# untitled.net
KiCad netlist of a schematic drawn in EAGLE
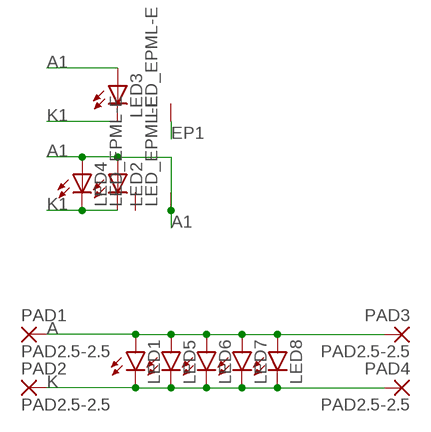
[diagram p0: schematic, sheet 1]

(export (version "E")
  (design (tool "Eeschema 10.0.6"))
  (components
    (comp (ref "LED1")
      (value "LEDSIDELED")
      (footprint "eagle-import:OSRAM-SIDELED")
      (libsource (lib "eagle-import") (part "LEDSIDELED"))
    )
    (comp (ref "LED2")
      (value "LED_EPML-E")
      (footprint "eagle-import:ML-E")
      (libsource (lib "eagle-import") (part "LED_EPML-E"))
    )
    (comp (ref "LED3")
      (value "LED_EPML-E")
      (footprint "eagle-import:ML-E")
      (libsource (lib "eagle-import") (part "LED_EPML-E"))
    )
    (comp (ref "LED4")
      (value "LED_EPML-E")
      (footprint "eagle-import:ML-E")
      (libsource (lib "eagle-import") (part "LED_EPML-E"))
    )
    (comp (ref "LED5")
      (value "LEDSIDELED")
      (footprint "eagle-import:OSRAM-SIDELED")
      (libsource (lib "eagle-import") (part "LEDSIDELED"))
    )
    (comp (ref "LED6")
      (value "LEDSIDELED")
      (footprint "eagle-import:OSRAM-SIDELED")
      (libsource (lib "eagle-import") (part "LEDSIDELED"))
    )
    (comp (ref "LED7")
      (value "LEDSIDELED")
      (footprint "eagle-import:OSRAM-SIDELED")
      (libsource (lib "eagle-import") (part "LEDSIDELED"))
    )
    (comp (ref "LED8")
      (value "LEDSIDELED")
      (footprint "eagle-import:OSRAM-SIDELED")
      (libsource (lib "eagle-import") (part "LEDSIDELED"))
    )
    (comp (ref "PAD1")
      (value "PAD2.5-2.5")
      (footprint "eagle-import:SMD2,5-2,5")
      (libsource (lib "eagle-import") (part "PAD2.5-2.5"))
    )
    (comp (ref "PAD2")
      (value "PAD2.5-2.5")
      (footprint "eagle-import:SMD2,5-2,5")
      (libsource (lib "eagle-import") (part "PAD2.5-2.5"))
    )
    (comp (ref "PAD3")
      (value "PAD2.5-2.5")
      (footprint "eagle-import:SMD2,5-2,5")
      (libsource (lib "eagle-import") (part "PAD2.5-2.5"))
    )
    (comp (ref "PAD4")
      (value "PAD2.5-2.5")
      (footprint "eagle-import:SMD2,5-2,5")
      (libsource (lib "eagle-import") (part "PAD2.5-2.5"))
    )
  )
  (nets
    (net (code "1") (name "/A") (class "Default")
      (node (ref "LED1") (pin "A") (pinfunction "A_A") (pintype "passive"))
      (node (ref "LED5") (pin "A") (pinfunction "A_A") (pintype "passive"))
      (node (ref "LED6") (pin "A") (pinfunction "A_A") (pintype "passive"))
      (node (ref "LED7") (pin "A") (pinfunction "A_A") (pintype "passive"))
      (node (ref "LED8") (pin "A") (pinfunction "A_A") (pintype "passive"))
      (node (ref "PAD1") (pin "1") (pinfunction "P_1") (pintype "passive"))
      (node (ref "PAD3") (pin "1") (pinfunction "P_1") (pintype "passive"))
    )
    (net (code "2") (name "/A1") (class "Default")
      (node (ref "LED2") (pin "A@1") (pinfunction "A_A@1") (pintype "passive"))
      (node (ref "LED2") (pin "A@2") (pinfunction "A_A@2") (pintype "passive"))
      (node (ref "LED2") (pin "TH") (pinfunction "EP_TH") (pintype "passive"))
      (node (ref "LED3") (pin "A@1") (pinfunction "A_A@1") (pintype "passive"))
      (node (ref "LED3") (pin "A@2") (pinfunction "A_A@2") (pintype "passive"))
      (node (ref "LED4") (pin "A@1") (pinfunction "A_A@1") (pintype "passive"))
      (node (ref "LED4") (pin "A@2") (pinfunction "A_A@2") (pintype "passive"))
    )
    (net (code "3") (name "/EP1") (class "Default")
      (node (ref "LED3") (pin "TH") (pinfunction "EP_TH") (pintype "passive"))
    )
    (net (code "4") (name "/K") (class "Default")
      (node (ref "LED1") (pin "C") (pinfunction "C_C") (pintype "passive"))
      (node (ref "LED5") (pin "C") (pinfunction "C_C") (pintype "passive"))
      (node (ref "LED6") (pin "C") (pinfunction "C_C") (pintype "passive"))
      (node (ref "LED7") (pin "C") (pinfunction "C_C") (pintype "passive"))
      (node (ref "LED8") (pin "C") (pinfunction "C_C") (pintype "passive"))
      (node (ref "PAD2") (pin "1") (pinfunction "P_1") (pintype "passive"))
      (node (ref "PAD4") (pin "1") (pinfunction "P_1") (pintype "passive"))
    )
    (net (code "5") (name "/K1") (class "Default")
      (node (ref "LED2") (pin "C@1") (pinfunction "C_C@1") (pintype "passive"))
      (node (ref "LED2") (pin "C@2") (pinfunction "C_C@2") (pintype "passive"))
      (node (ref "LED3") (pin "C@1") (pinfunction "C_C@1") (pintype "passive"))
      (node (ref "LED3") (pin "C@2") (pinfunction "C_C@2") (pintype "passive"))
      (node (ref "LED4") (pin "C@1") (pinfunction "C_C@1") (pintype "passive"))
      (node (ref "LED4") (pin "C@2") (pinfunction "C_C@2") (pintype "passive"))
    )
    (net (code "6") (name "unconnected-(LED4-EP-PadTH)") (class "Default")
      (node (ref "LED4") (pin "TH") (pinfunction "EP_TH") (pintype "passive"))
    )
  )
)
